# 4_waffling60-MXHS-ISO_periferals.net
KiCad netlist of a schematic drawn in Altium Designer
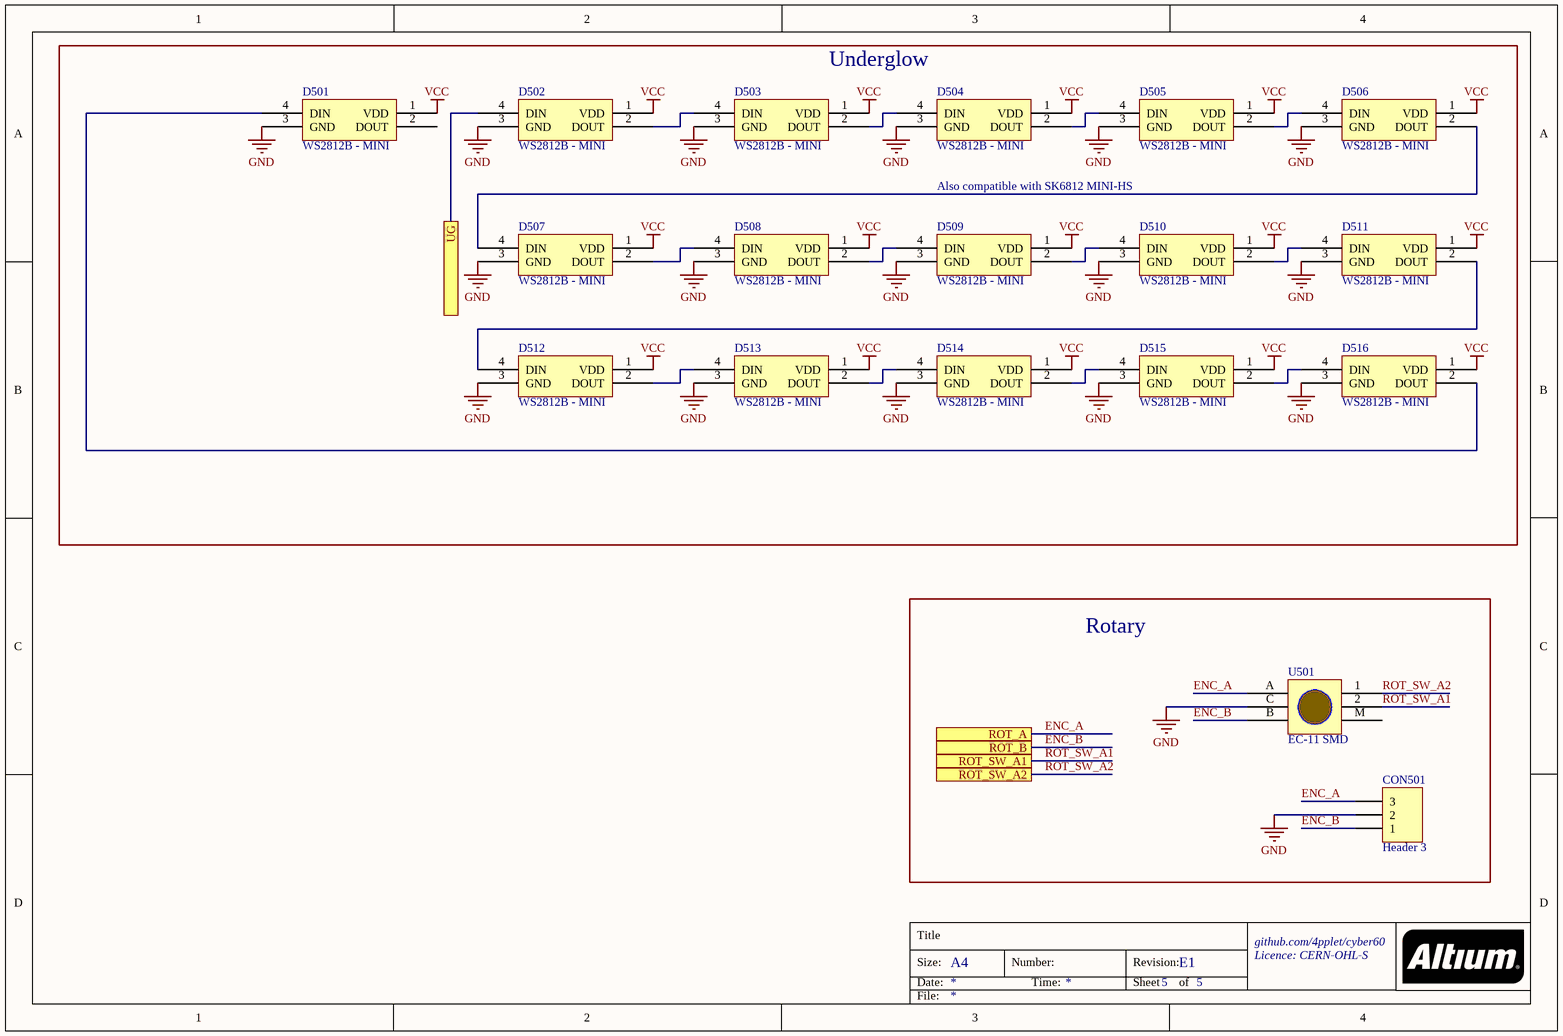
[diagram p0: 4_waffling60-MXHS-ISO_periferals.SchDoc]

(export (version "E")
  (design (tool "Eeschema 10.0.6"))
  (components
    (comp (ref "CON501")
      (value "Header 3")
      (footprint "HDR1X3")
      (description "Header, 3-Pin")
      (libsource (lib "Miscellaneous Connectors") (part "Header 3"))
    )
    (comp (ref "D501")
      (value "WS2812B - MINI")
      (footprint "WS2812B - 2020")
      (fields (field (name "LCSC PART #") "C965555") (field (name "MRF.PART") "WS2812B-2020"))
      (libsource (lib "Keebs") (part "WS2812B"))
    )
    (comp (ref "D502")
      (value "WS2812B - MINI")
      (footprint "WS2812B - 2020")
      (fields (field (name "LCSC PART #") "C965555") (field (name "MRF.PART") "WS2812B-2020"))
      (libsource (lib "Keebs") (part "WS2812B"))
    )
    (comp (ref "D503")
      (value "WS2812B - MINI")
      (footprint "WS2812B - 2020")
      (fields (field (name "LCSC PART #") "C965555") (field (name "MRF.PART") "WS2812B-2020"))
      (libsource (lib "Keebs") (part "WS2812B"))
    )
    (comp (ref "D504")
      (value "WS2812B - MINI")
      (footprint "WS2812B - 2020")
      (fields (field (name "LCSC PART #") "C965555") (field (name "MRF.PART") "WS2812B-2020"))
      (libsource (lib "Keebs") (part "WS2812B"))
    )
    (comp (ref "D505")
      (value "WS2812B - MINI")
      (footprint "WS2812B - 2020")
      (fields (field (name "LCSC PART #") "C965555") (field (name "MRF.PART") "WS2812B-2020"))
      (libsource (lib "Keebs") (part "WS2812B"))
    )
    (comp (ref "D506")
      (value "WS2812B - MINI")
      (footprint "WS2812B - 2020")
      (fields (field (name "LCSC PART #") "C965555") (field (name "MRF.PART") "WS2812B-2020"))
      (libsource (lib "Keebs") (part "WS2812B"))
    )
    (comp (ref "D507")
      (value "WS2812B - MINI")
      (footprint "WS2812B - 2020")
      (fields (field (name "LCSC PART #") "C965555") (field (name "MRF.PART") "WS2812B-2020"))
      (libsource (lib "Keebs") (part "WS2812B"))
    )
    (comp (ref "D508")
      (value "WS2812B - MINI")
      (footprint "WS2812B - 2020")
      (fields (field (name "LCSC PART #") "C965555") (field (name "MRF.PART") "WS2812B-2020"))
      (libsource (lib "Keebs") (part "WS2812B"))
    )
    (comp (ref "D509")
      (value "WS2812B - MINI")
      (footprint "WS2812B - 2020")
      (fields (field (name "LCSC PART #") "C965555") (field (name "MRF.PART") "WS2812B-2020"))
      (libsource (lib "Keebs") (part "WS2812B"))
    )
    (comp (ref "D510")
      (value "WS2812B - MINI")
      (footprint "WS2812B - 2020")
      (fields (field (name "LCSC PART #") "C965555") (field (name "MRF.PART") "WS2812B-2020"))
      (libsource (lib "Keebs") (part "WS2812B"))
    )
    (comp (ref "D511")
      (value "WS2812B - MINI")
      (footprint "WS2812B - 2020")
      (fields (field (name "LCSC PART #") "C965555") (field (name "MRF.PART") "WS2812B-2020"))
      (libsource (lib "Keebs") (part "WS2812B"))
    )
    (comp (ref "D512")
      (value "WS2812B - MINI")
      (footprint "WS2812B - 2020")
      (fields (field (name "LCSC PART #") "C965555") (field (name "MRF.PART") "WS2812B-2020"))
      (libsource (lib "Keebs") (part "WS2812B"))
    )
    (comp (ref "D513")
      (value "WS2812B - MINI")
      (footprint "WS2812B - 2020")
      (fields (field (name "LCSC PART #") "C965555") (field (name "MRF.PART") "WS2812B-2020"))
      (libsource (lib "Keebs") (part "WS2812B"))
    )
    (comp (ref "D514")
      (value "WS2812B - MINI")
      (footprint "WS2812B - 2020")
      (fields (field (name "LCSC PART #") "C965555") (field (name "MRF.PART") "WS2812B-2020"))
      (libsource (lib "Keebs") (part "WS2812B"))
    )
    (comp (ref "D515")
      (value "WS2812B - MINI")
      (footprint "WS2812B - 2020")
      (fields (field (name "LCSC PART #") "C965555") (field (name "MRF.PART") "WS2812B-2020"))
      (libsource (lib "Keebs") (part "WS2812B"))
    )
    (comp (ref "D516")
      (value "WS2812B - MINI")
      (footprint "WS2812B - 2020")
      (fields (field (name "LCSC PART #") "C965555") (field (name "MRF.PART") "WS2812B-2020"))
      (libsource (lib "Keebs") (part "WS2812B"))
    )
    (comp (ref "U501") (value "EC-11 SMD") (footprint "EC11-SMD") (libsource (lib "Keebs") (part "EC-11")))
  )
  (nets
    (net (code "1") (name "/ENC_A") (class "Default")
      (node (ref "CON501") (pin "3") (pinfunction "3_3") (pintype "passive"))
      (node (ref "U501") (pin "A") (pinfunction "B_A") (pintype "passive"))
    )
    (net (code "2") (name "/ENC_B") (class "Default")
      (node (ref "CON501") (pin "1") (pinfunction "1_1") (pintype "passive"))
      (node (ref "U501") (pin "B") (pinfunction "B_B") (pintype "passive"))
    )
    (net (code "3") (name "/ROT_SW_A1") (class "Default")
      (node (ref "U501") (pin "2") (pinfunction "2_2") (pintype "passive"))
    )
    (net (code "4") (name "/ROT_SW_A2") (class "Default")
      (node (ref "U501") (pin "1") (pinfunction "1_1") (pintype "passive"))
    )
    (net (code "5") (name "/UG") (class "Default")
      (node (ref "D502") (pin "4") (pinfunction "DIN_4") (pintype "passive"))
    )
    (net (code "6") (name "GND") (class "Default")
      (node (ref "CON501") (pin "2") (pinfunction "2_2") (pintype "passive"))
      (node (ref "D501") (pin "3") (pinfunction "GND_3") (pintype "passive"))
      (node (ref "D502") (pin "3") (pinfunction "GND_3") (pintype "passive"))
      (node (ref "D503") (pin "3") (pinfunction "GND_3") (pintype "passive"))
      (node (ref "D504") (pin "3") (pinfunction "GND_3") (pintype "passive"))
      (node (ref "D505") (pin "3") (pinfunction "GND_3") (pintype "passive"))
      (node (ref "D506") (pin "3") (pinfunction "GND_3") (pintype "passive"))
      (node (ref "D507") (pin "3") (pinfunction "GND_3") (pintype "passive"))
      (node (ref "D508") (pin "3") (pinfunction "GND_3") (pintype "passive"))
      (node (ref "D509") (pin "3") (pinfunction "GND_3") (pintype "passive"))
      (node (ref "D510") (pin "3") (pinfunction "GND_3") (pintype "passive"))
      (node (ref "D511") (pin "3") (pinfunction "GND_3") (pintype "passive"))
      (node (ref "D512") (pin "3") (pinfunction "GND_3") (pintype "passive"))
      (node (ref "D513") (pin "3") (pinfunction "GND_3") (pintype "passive"))
      (node (ref "D514") (pin "3") (pinfunction "GND_3") (pintype "passive"))
      (node (ref "D515") (pin "3") (pinfunction "GND_3") (pintype "passive"))
      (node (ref "D516") (pin "3") (pinfunction "GND_3") (pintype "passive"))
      (node (ref "U501") (pin "C") (pinfunction "C_C") (pintype "passive"))
    )
    (net (code "7") (name "Net-(D501-DIN)") (class "Default")
      (node (ref "D501") (pin "4") (pinfunction "DIN_4") (pintype "passive"))
      (node (ref "D516") (pin "2") (pinfunction "DOUT_2") (pintype "passive"))
    )
    (net (code "8") (name "Net-(D502-DOUT)") (class "Default")
      (node (ref "D502") (pin "2") (pinfunction "DOUT_2") (pintype "passive"))
      (node (ref "D503") (pin "4") (pinfunction "DIN_4") (pintype "passive"))
    )
    (net (code "9") (name "Net-(D503-DOUT)") (class "Default")
      (node (ref "D503") (pin "2") (pinfunction "DOUT_2") (pintype "passive"))
      (node (ref "D504") (pin "4") (pinfunction "DIN_4") (pintype "passive"))
    )
    (net (code "10") (name "Net-(D504-DOUT)") (class "Default")
      (node (ref "D504") (pin "2") (pinfunction "DOUT_2") (pintype "passive"))
      (node (ref "D505") (pin "4") (pinfunction "DIN_4") (pintype "passive"))
    )
    (net (code "11") (name "Net-(D505-DOUT)") (class "Default")
      (node (ref "D505") (pin "2") (pinfunction "DOUT_2") (pintype "passive"))
      (node (ref "D506") (pin "4") (pinfunction "DIN_4") (pintype "passive"))
    )
    (net (code "12") (name "Net-(D506-DOUT)") (class "Default")
      (node (ref "D506") (pin "2") (pinfunction "DOUT_2") (pintype "passive"))
      (node (ref "D507") (pin "4") (pinfunction "DIN_4") (pintype "passive"))
    )
    (net (code "13") (name "Net-(D507-DOUT)") (class "Default")
      (node (ref "D507") (pin "2") (pinfunction "DOUT_2") (pintype "passive"))
      (node (ref "D508") (pin "4") (pinfunction "DIN_4") (pintype "passive"))
    )
    (net (code "14") (name "Net-(D508-DOUT)") (class "Default")
      (node (ref "D508") (pin "2") (pinfunction "DOUT_2") (pintype "passive"))
      (node (ref "D509") (pin "4") (pinfunction "DIN_4") (pintype "passive"))
    )
    (net (code "15") (name "Net-(D509-DOUT)") (class "Default")
      (node (ref "D509") (pin "2") (pinfunction "DOUT_2") (pintype "passive"))
      (node (ref "D510") (pin "4") (pinfunction "DIN_4") (pintype "passive"))
    )
    (net (code "16") (name "Net-(D510-DOUT)") (class "Default")
      (node (ref "D510") (pin "2") (pinfunction "DOUT_2") (pintype "passive"))
      (node (ref "D511") (pin "4") (pinfunction "DIN_4") (pintype "passive"))
    )
    (net (code "17") (name "Net-(D511-DOUT)") (class "Default")
      (node (ref "D511") (pin "2") (pinfunction "DOUT_2") (pintype "passive"))
      (node (ref "D512") (pin "4") (pinfunction "DIN_4") (pintype "passive"))
    )
    (net (code "18") (name "Net-(D512-DOUT)") (class "Default")
      (node (ref "D512") (pin "2") (pinfunction "DOUT_2") (pintype "passive"))
      (node (ref "D513") (pin "4") (pinfunction "DIN_4") (pintype "passive"))
    )
    (net (code "19") (name "Net-(D513-DOUT)") (class "Default")
      (node (ref "D513") (pin "2") (pinfunction "DOUT_2") (pintype "passive"))
      (node (ref "D514") (pin "4") (pinfunction "DIN_4") (pintype "passive"))
    )
    (net (code "20") (name "Net-(D514-DOUT)") (class "Default")
      (node (ref "D514") (pin "2") (pinfunction "DOUT_2") (pintype "passive"))
      (node (ref "D515") (pin "4") (pinfunction "DIN_4") (pintype "passive"))
    )
    (net (code "21") (name "Net-(D515-DOUT)") (class "Default")
      (node (ref "D515") (pin "2") (pinfunction "DOUT_2") (pintype "passive"))
      (node (ref "D516") (pin "4") (pinfunction "DIN_4") (pintype "passive"))
    )
    (net (code "22") (name "VCC") (class "Default")
      (node (ref "D501") (pin "1") (pinfunction "VDD_1") (pintype "passive"))
      (node (ref "D502") (pin "1") (pinfunction "VDD_1") (pintype "passive"))
      (node (ref "D503") (pin "1") (pinfunction "VDD_1") (pintype "passive"))
      (node (ref "D504") (pin "1") (pinfunction "VDD_1") (pintype "passive"))
      (node (ref "D505") (pin "1") (pinfunction "VDD_1") (pintype "passive"))
      (node (ref "D506") (pin "1") (pinfunction "VDD_1") (pintype "passive"))
      (node (ref "D507") (pin "1") (pinfunction "VDD_1") (pintype "passive"))
      (node (ref "D508") (pin "1") (pinfunction "VDD_1") (pintype "passive"))
      (node (ref "D509") (pin "1") (pinfunction "VDD_1") (pintype "passive"))
      (node (ref "D510") (pin "1") (pinfunction "VDD_1") (pintype "passive"))
      (node (ref "D511") (pin "1") (pinfunction "VDD_1") (pintype "passive"))
      (node (ref "D512") (pin "1") (pinfunction "VDD_1") (pintype "passive"))
      (node (ref "D513") (pin "1") (pinfunction "VDD_1") (pintype "passive"))
      (node (ref "D514") (pin "1") (pinfunction "VDD_1") (pintype "passive"))
      (node (ref "D515") (pin "1") (pinfunction "VDD_1") (pintype "passive"))
      (node (ref "D516") (pin "1") (pinfunction "VDD_1") (pintype "passive"))
    )
    (net (code "23") (name "unconnected-(D501-DOUT-Pad2)") (class "Default")
      (node (ref "D501") (pin "2") (pinfunction "DOUT_2") (pintype "passive"))
    )
    (net (code "24") (name "unconnected-(U501-PadM)") (class "Default")
      (node (ref "U501") (pin "M") (pinfunction "M_M") (pintype "passive"))
    )
  )
)
